# Mixer-Analog-OPA2134-Rev-G.net
KiCad netlist of a schematic drawn in EAGLE
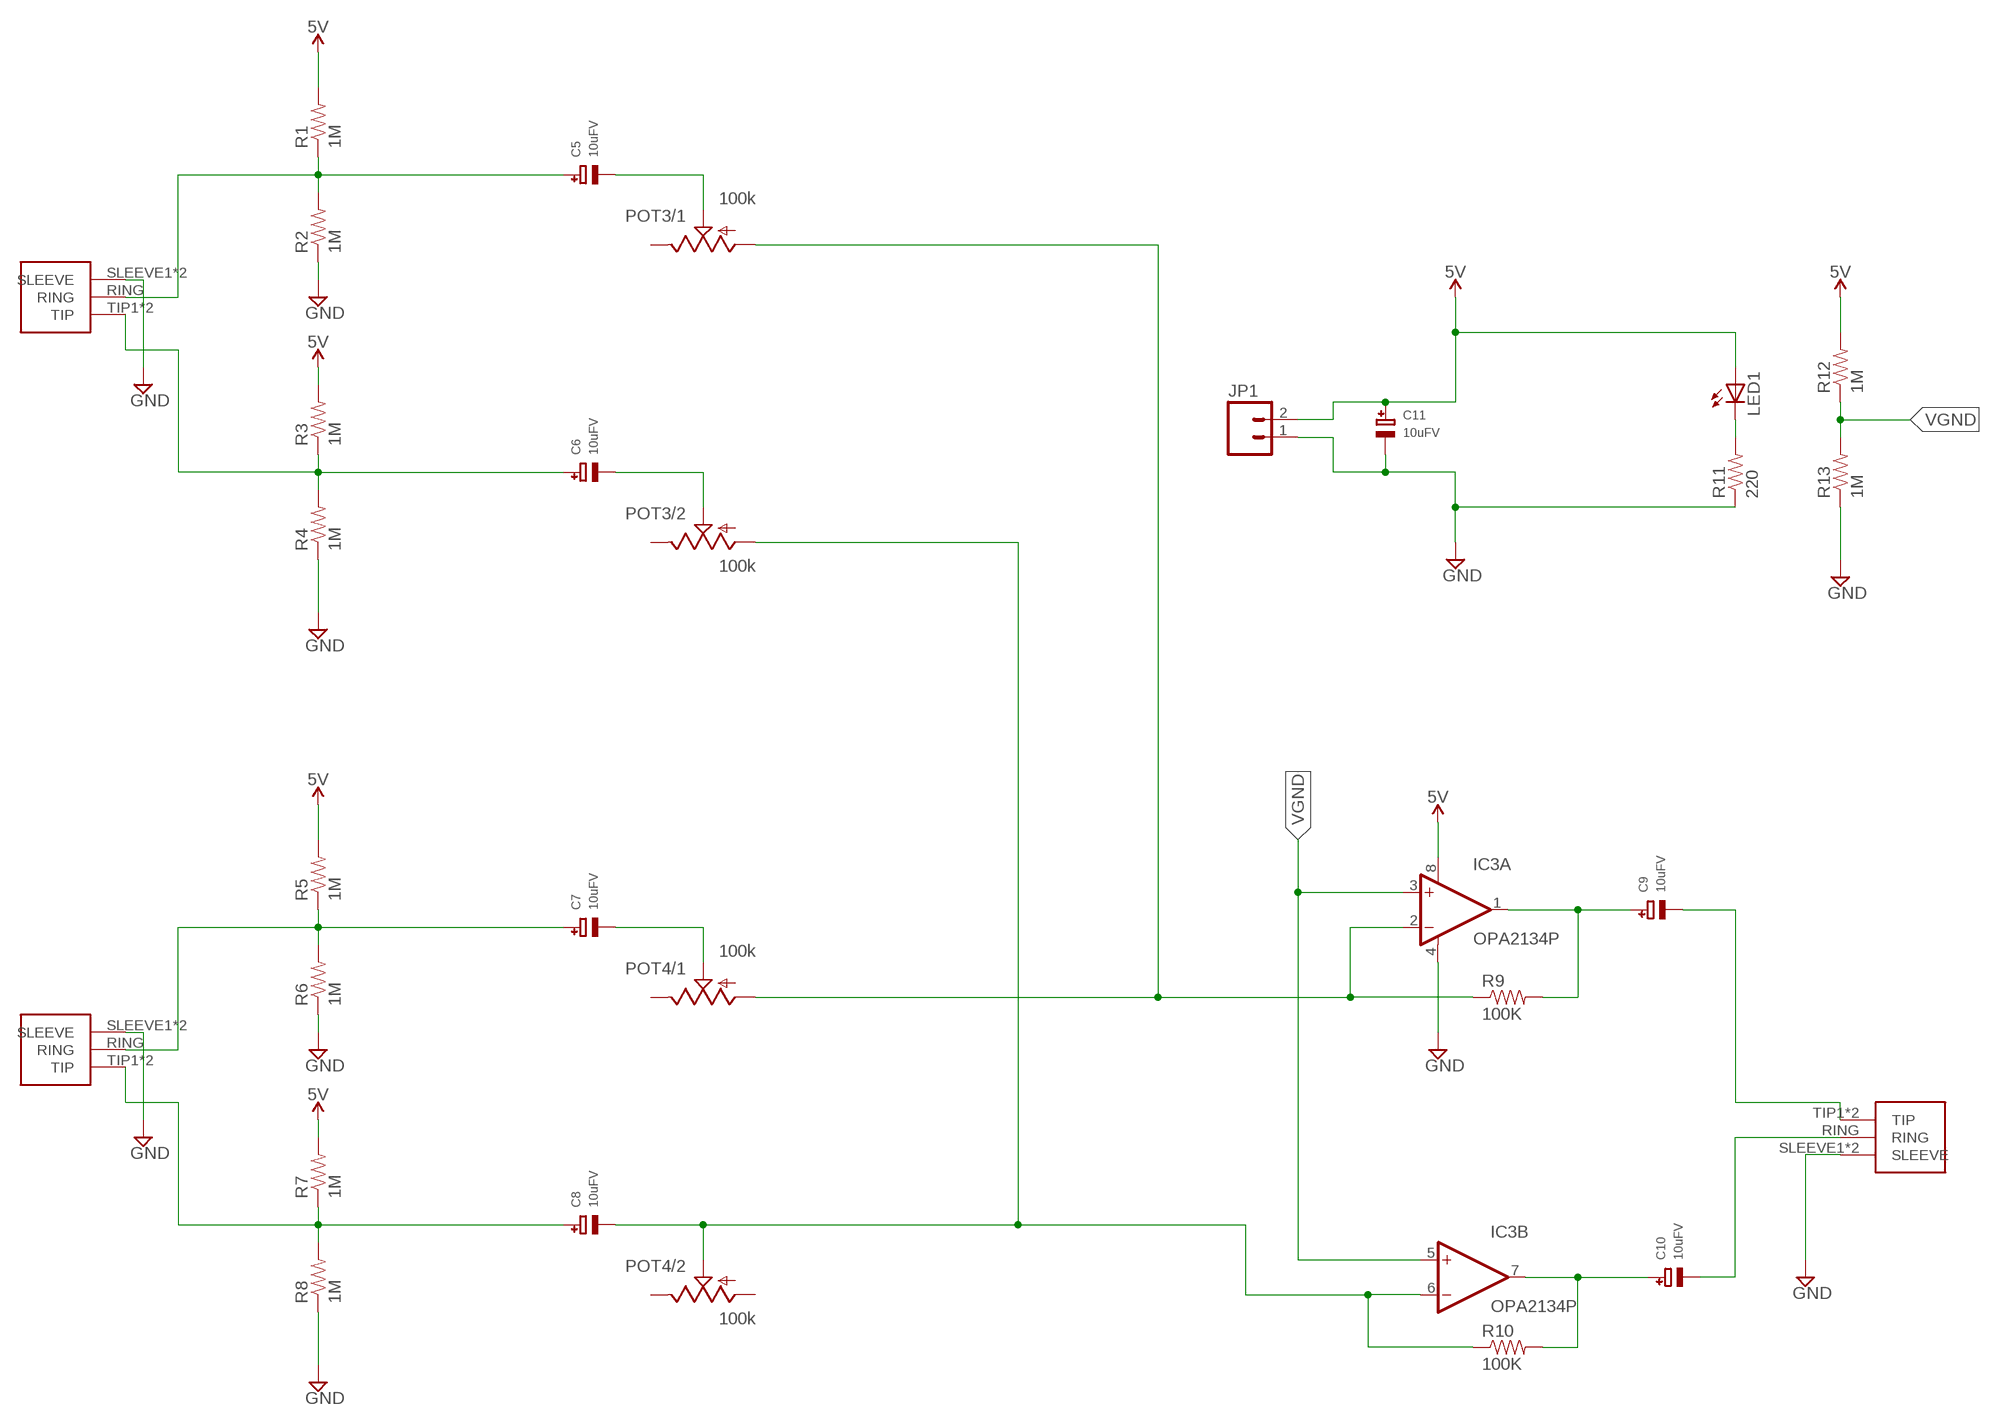
[diagram p0: schematic, sheet 1]

(export (version "E")
  (design (tool "Eeschema 10.0.6"))
  (components
    (comp (ref "C5")
      (value "10uFV")
      (footprint "eagle-import:CELEC_3.5MM_8MM")
      (libsource (lib "eagle-import") (part "CAP_ELECTROLYTICPTH_3.5MMGRID_8MMDIA"))
    )
    (comp (ref "C6")
      (value "10uFV")
      (footprint "eagle-import:CELEC_3.5MM_8MM")
      (libsource (lib "eagle-import") (part "CAP_ELECTROLYTICPTH_3.5MMGRID_8MMDIA"))
    )
    (comp (ref "C7")
      (value "10uFV")
      (footprint "eagle-import:CELEC_3.5MM_8MM")
      (libsource (lib "eagle-import") (part "CAP_ELECTROLYTICPTH_3.5MMGRID_8MMDIA"))
    )
    (comp (ref "C8")
      (value "10uFV")
      (footprint "eagle-import:CELEC_3.5MM_8MM")
      (libsource (lib "eagle-import") (part "CAP_ELECTROLYTICPTH_3.5MMGRID_8MMDIA"))
    )
    (comp (ref "C9")
      (value "10uFV")
      (footprint "eagle-import:CELEC_3.5MM_8MM")
      (libsource (lib "eagle-import") (part "CAP_ELECTROLYTICPTH_3.5MMGRID_8MMDIA"))
    )
    (comp (ref "C10")
      (value "10uFV")
      (footprint "eagle-import:CELEC_3.5MM_8MM")
      (libsource (lib "eagle-import") (part "CAP_ELECTROLYTICPTH_3.5MMGRID_8MMDIA"))
    )
    (comp (ref "C11")
      (value "10uFV")
      (footprint "eagle-import:CELEC_3.5MM_8MM")
      (libsource (lib "eagle-import") (part "CAP_ELECTROLYTICPTH_3.5MMGRID_8MMDIA"))
    )
    (comp (ref "IC3")
      (value "OPA2134P")
      (footprint "eagle-import:DIL08")
      (fields (field (name "MF") "TEXAS INSTRUMENTS") (field (name "MPN") "OPA2134PA"))
      (libsource (lib "eagle-import") (part "OPA2134P"))
    )
    (comp (ref "J1")
      (value "1/8\"-F-STEREO-PCB")
      (footprint "eagle-import:1_8_-F-STEREO-PCB")
      (libsource (lib "eagle-import") (part "1/8{dblquote}-F-STEREO-PCB"))
    )
    (comp (ref "J2")
      (value "1/8\"-F-STEREO-PCB")
      (footprint "eagle-import:1_8_-F-STEREO-PCB")
      (libsource (lib "eagle-import") (part "1/8{dblquote}-F-STEREO-PCB"))
    )
    (comp (ref "J3")
      (value "1/8\"-F-STEREO-PCB")
      (footprint "eagle-import:1_8_-F-STEREO-PCB")
      (libsource (lib "eagle-import") (part "1/8{dblquote}-F-STEREO-PCB"))
    )
    (comp (ref "JP1")
      (value "M02LOCK")
      (footprint "eagle-import:1X02_LOCK")
      (libsource (lib "eagle-import") (part "M02LOCK"))
    )
    (comp (ref "LED1")
      (value "LED3MM")
      (footprint "eagle-import:LED3MM")
      (libsource (lib "eagle-import") (part "LED3MM"))
    )
    (comp (ref "POT3")
      (value "100k")
      (footprint "eagle-import:PTV112")
      (fields
        (field (name "MF") "STMicroelectronics")
        (field (name "MP") "PTV112")
        (field (name "SPICEPREFIX") "J")
      )
      (libsource (lib "eagle-import") (part "POT-DUAL-PTV112-4420"))
    )
    (comp (ref "POT4")
      (value "100k")
      (footprint "eagle-import:PTV112")
      (fields
        (field (name "MF") "STMicroelectronics")
        (field (name "MP") "PTV112")
        (field (name "SPICEPREFIX") "J")
      )
      (libsource (lib "eagle-import") (part "POT-DUAL-PTV112-4420"))
    )
    (comp (ref "R1")
      (value "1M")
      (footprint "eagle-import:AXIAL-0.3EZ")
      (fields (field (name "SPICEPREFIX") "R"))
      (libsource (lib "eagle-import") (part "RESISTOREZ"))
    )
    (comp (ref "R2")
      (value "1M")
      (footprint "eagle-import:AXIAL-0.3")
      (fields (field (name "SPICEPREFIX") "R"))
      (libsource (lib "eagle-import") (part "RESISTORAXIAL-0.3"))
    )
    (comp (ref "R3")
      (value "1M")
      (footprint "eagle-import:AXIAL-0.3EZ")
      (fields (field (name "SPICEPREFIX") "R"))
      (libsource (lib "eagle-import") (part "RESISTOREZ"))
    )
    (comp (ref "R4")
      (value "1M")
      (footprint "eagle-import:AXIAL-0.3EZ")
      (fields (field (name "SPICEPREFIX") "R"))
      (libsource (lib "eagle-import") (part "RESISTOREZ"))
    )
    (comp (ref "R5")
      (value "1M")
      (footprint "eagle-import:AXIAL-0.3EZ")
      (fields (field (name "SPICEPREFIX") "R"))
      (libsource (lib "eagle-import") (part "RESISTOREZ"))
    )
    (comp (ref "R6")
      (value "1M")
      (footprint "eagle-import:AXIAL-0.3EZ")
      (fields (field (name "SPICEPREFIX") "R"))
      (libsource (lib "eagle-import") (part "RESISTOREZ"))
    )
    (comp (ref "R7")
      (value "1M")
      (footprint "eagle-import:AXIAL-0.3EZ")
      (fields (field (name "SPICEPREFIX") "R"))
      (libsource (lib "eagle-import") (part "RESISTOREZ"))
    )
    (comp (ref "R8")
      (value "1M")
      (footprint "eagle-import:AXIAL-0.3EZ")
      (fields (field (name "SPICEPREFIX") "R"))
      (libsource (lib "eagle-import") (part "RESISTOREZ"))
    )
    (comp (ref "R9")
      (value "100K")
      (footprint "eagle-import:AXIAL-0.3EZ")
      (fields (field (name "SPICEPREFIX") "R"))
      (libsource (lib "eagle-import") (part "RESISTOREZ"))
    )
    (comp (ref "R10")
      (value "100K")
      (footprint "eagle-import:AXIAL-0.3EZ")
      (fields (field (name "SPICEPREFIX") "R"))
      (libsource (lib "eagle-import") (part "RESISTOREZ"))
    )
    (comp (ref "R11")
      (value "220")
      (footprint "eagle-import:AXIAL-0.3EZ")
      (libsource (lib "eagle-import") (part "RESISTOREZ"))
    )
    (comp (ref "R12")
      (value "1M")
      (footprint "eagle-import:AXIAL-0.3EZ")
      (libsource (lib "eagle-import") (part "RESISTOREZ"))
    )
    (comp (ref "R13")
      (value "1M")
      (footprint "eagle-import:AXIAL-0.3EZ")
      (libsource (lib "eagle-import") (part "RESISTOREZ"))
    )
  )
  (nets
    (net (code "1") (name "5V") (class "Default")
      (node (ref "C11") (pin "+") (pinfunction "+_+") (pintype "passive"))
      (node (ref "IC3") (pin "8") (pinfunction "V+_8") (pintype "power_in"))
      (node (ref "JP1") (pin "2") (pinfunction "2_2") (pintype "passive"))
      (node (ref "LED1") (pin "A") (pinfunction "A_A") (pintype "passive"))
      (node (ref "R1") (pin "P$2") (pinfunction "2_P$2") (pintype "passive"))
      (node (ref "R12") (pin "P$2") (pinfunction "2_P$2") (pintype "passive"))
      (node (ref "R3") (pin "P$2") (pinfunction "2_P$2") (pintype "passive"))
      (node (ref "R5") (pin "P$2") (pinfunction "2_P$2") (pintype "passive"))
      (node (ref "R7") (pin "P$2") (pinfunction "2_P$2") (pintype "passive"))
    )
    (net (code "2") (name "GND") (class "Default")
      (node (ref "C11") (pin "-") (pinfunction "-_-") (pintype "passive"))
      (node (ref "IC3") (pin "4") (pinfunction "V-_4") (pintype "power_in"))
      (node (ref "J1") (pin "SLEEVE1") (pinfunction "SLEEVE_SLEEVE1") (pintype "bidirectional"))
      (node (ref "J1") (pin "SLEEVE2") (pinfunction "SLEEVE_SLEEVE2") (pintype "bidirectional"))
      (node (ref "J2") (pin "SLEEVE1") (pinfunction "SLEEVE_SLEEVE1") (pintype "bidirectional"))
      (node (ref "J2") (pin "SLEEVE2") (pinfunction "SLEEVE_SLEEVE2") (pintype "bidirectional"))
      (node (ref "J3") (pin "SLEEVE1") (pinfunction "SLEEVE_SLEEVE1") (pintype "bidirectional"))
      (node (ref "J3") (pin "SLEEVE2") (pinfunction "SLEEVE_SLEEVE2") (pintype "bidirectional"))
      (node (ref "JP1") (pin "1") (pinfunction "1_1") (pintype "passive"))
      (node (ref "R11") (pin "P$1") (pinfunction "1_P$1") (pintype "passive"))
      (node (ref "R13") (pin "P$1") (pinfunction "1_P$1") (pintype "passive"))
      (node (ref "R2") (pin "P$1") (pinfunction "1_P$1") (pintype "passive"))
      (node (ref "R4") (pin "P$1") (pinfunction "1_P$1") (pintype "passive"))
      (node (ref "R6") (pin "P$1") (pinfunction "1_P$1") (pintype "passive"))
      (node (ref "R8") (pin "P$1") (pinfunction "1_P$1") (pintype "passive"))
    )
    (net (code "3") (name "Net-(C9-Pad-)") (class "Default")
      (node (ref "C9") (pin "-") (pinfunction "-_-") (pintype "passive"))
      (node (ref "J3") (pin "TIP1") (pinfunction "TIP_TIP1") (pintype "bidirectional"))
      (node (ref "J3") (pin "TIP2") (pinfunction "TIP_TIP2") (pintype "bidirectional"))
    )
    (net (code "4") (name "Net-(C10-Pad-)") (class "Default")
      (node (ref "C10") (pin "-") (pinfunction "-_-") (pintype "passive"))
      (node (ref "J3") (pin "RING") (pinfunction "RING_RING") (pintype "bidirectional"))
    )
    (net (code "5") (name "Net-(IC3A--IN)") (class "Default")
      (node (ref "IC3") (pin "2") (pinfunction "-IN_2") (pintype "input"))
      (node (ref "POT3") (pin "1.1") (pinfunction "A_1.1") (pintype "passive"))
      (node (ref "POT4") (pin "1.1") (pinfunction "A_1.1") (pintype "passive"))
      (node (ref "R9") (pin "P$1") (pinfunction "1_P$1") (pintype "passive"))
    )
    (net (code "6") (name "Net-(IC3A-OUT)") (class "Default")
      (node (ref "C9") (pin "+") (pinfunction "+_+") (pintype "passive"))
      (node (ref "IC3") (pin "1") (pinfunction "OUT_1") (pintype "output"))
      (node (ref "R9") (pin "P$2") (pinfunction "2_P$2") (pintype "passive"))
    )
    (net (code "7") (name "Net-(IC3B--IN)") (class "Default")
      (node (ref "C8") (pin "-") (pinfunction "-_-") (pintype "passive"))
      (node (ref "IC3") (pin "6") (pinfunction "-IN_6") (pintype "input"))
      (node (ref "POT3") (pin "2.1") (pinfunction "A_2.1") (pintype "passive"))
      (node (ref "POT4") (pin "2.2") (pinfunction "S_2.2") (pintype "passive"))
      (node (ref "R10") (pin "P$1") (pinfunction "1_P$1") (pintype "passive"))
    )
    (net (code "8") (name "Net-(IC3B-OUT)") (class "Default")
      (node (ref "C10") (pin "+") (pinfunction "+_+") (pintype "passive"))
      (node (ref "IC3") (pin "7") (pinfunction "OUT_7") (pintype "output"))
      (node (ref "R10") (pin "P$2") (pinfunction "2_P$2") (pintype "passive"))
    )
    (net (code "9") (name "Net-(LED1-C)") (class "Default")
      (node (ref "LED1") (pin "K") (pinfunction "C_K") (pintype "passive"))
      (node (ref "R11") (pin "P$2") (pinfunction "2_P$2") (pintype "passive"))
    )
    (net (code "10") (name "Net-(POT3A-S)") (class "Default")
      (node (ref "C5") (pin "-") (pinfunction "-_-") (pintype "passive"))
      (node (ref "POT3") (pin "1.2") (pinfunction "S_1.2") (pintype "passive"))
    )
    (net (code "11") (name "Net-(POT3B-S)") (class "Default")
      (node (ref "C6") (pin "-") (pinfunction "-_-") (pintype "passive"))
      (node (ref "POT3") (pin "2.2") (pinfunction "S_2.2") (pintype "passive"))
    )
    (net (code "12") (name "Net-(POT4A-S)") (class "Default")
      (node (ref "C7") (pin "-") (pinfunction "-_-") (pintype "passive"))
      (node (ref "POT4") (pin "1.2") (pinfunction "S_1.2") (pintype "passive"))
    )
    (net (code "13") (name "Net-(R1-1)") (class "Default")
      (node (ref "C5") (pin "+") (pinfunction "+_+") (pintype "passive"))
      (node (ref "J1") (pin "RING") (pinfunction "RING_RING") (pintype "bidirectional"))
      (node (ref "R1") (pin "P$1") (pinfunction "1_P$1") (pintype "passive"))
      (node (ref "R2") (pin "P$2") (pinfunction "2_P$2") (pintype "passive"))
    )
    (net (code "14") (name "Net-(R3-1)") (class "Default")
      (node (ref "C6") (pin "+") (pinfunction "+_+") (pintype "passive"))
      (node (ref "J1") (pin "TIP1") (pinfunction "TIP_TIP1") (pintype "bidirectional"))
      (node (ref "J1") (pin "TIP2") (pinfunction "TIP_TIP2") (pintype "bidirectional"))
      (node (ref "R3") (pin "P$1") (pinfunction "1_P$1") (pintype "passive"))
      (node (ref "R4") (pin "P$2") (pinfunction "2_P$2") (pintype "passive"))
    )
    (net (code "15") (name "Net-(R5-1)") (class "Default")
      (node (ref "C7") (pin "+") (pinfunction "+_+") (pintype "passive"))
      (node (ref "J2") (pin "RING") (pinfunction "RING_RING") (pintype "bidirectional"))
      (node (ref "R5") (pin "P$1") (pinfunction "1_P$1") (pintype "passive"))
      (node (ref "R6") (pin "P$2") (pinfunction "2_P$2") (pintype "passive"))
    )
    (net (code "16") (name "Net-(R7-1)") (class "Default")
      (node (ref "C8") (pin "+") (pinfunction "+_+") (pintype "passive"))
      (node (ref "J2") (pin "TIP1") (pinfunction "TIP_TIP1") (pintype "bidirectional"))
      (node (ref "J2") (pin "TIP2") (pinfunction "TIP_TIP2") (pintype "bidirectional"))
      (node (ref "R7") (pin "P$1") (pinfunction "1_P$1") (pintype "passive"))
      (node (ref "R8") (pin "P$2") (pinfunction "2_P$2") (pintype "passive"))
    )
    (net (code "17") (name "VGND") (class "Default")
      (node (ref "IC3") (pin "3") (pinfunction "+IN_3") (pintype "input"))
      (node (ref "IC3") (pin "5") (pinfunction "+IN_5") (pintype "input"))
      (node (ref "R12") (pin "P$1") (pinfunction "1_P$1") (pintype "passive"))
      (node (ref "R13") (pin "P$2") (pinfunction "2_P$2") (pintype "passive"))
    )
    (net (code "18") (name "unconnected-(POT3A-E-Pad1.3)") (class "Default")
      (node (ref "POT3") (pin "1.3") (pinfunction "E_1.3") (pintype "passive"))
    )
    (net (code "19") (name "unconnected-(POT3B-E-Pad2.3)") (class "Default")
      (node (ref "POT3") (pin "2.3") (pinfunction "E_2.3") (pintype "passive"))
    )
    (net (code "20") (name "unconnected-(POT4A-E-Pad1.3)") (class "Default")
      (node (ref "POT4") (pin "1.3") (pinfunction "E_1.3") (pintype "passive"))
    )
    (net (code "21") (name "unconnected-(POT4B-A-Pad2.1)") (class "Default")
      (node (ref "POT4") (pin "2.1") (pinfunction "A_2.1") (pintype "passive"))
    )
    (net (code "22") (name "unconnected-(POT4B-E-Pad2.3)") (class "Default")
      (node (ref "POT4") (pin "2.3") (pinfunction "E_2.3") (pintype "passive"))
    )
  )
)
